# hud_v300_MCU.net
KiCad netlist of a schematic drawn in Altium Designer
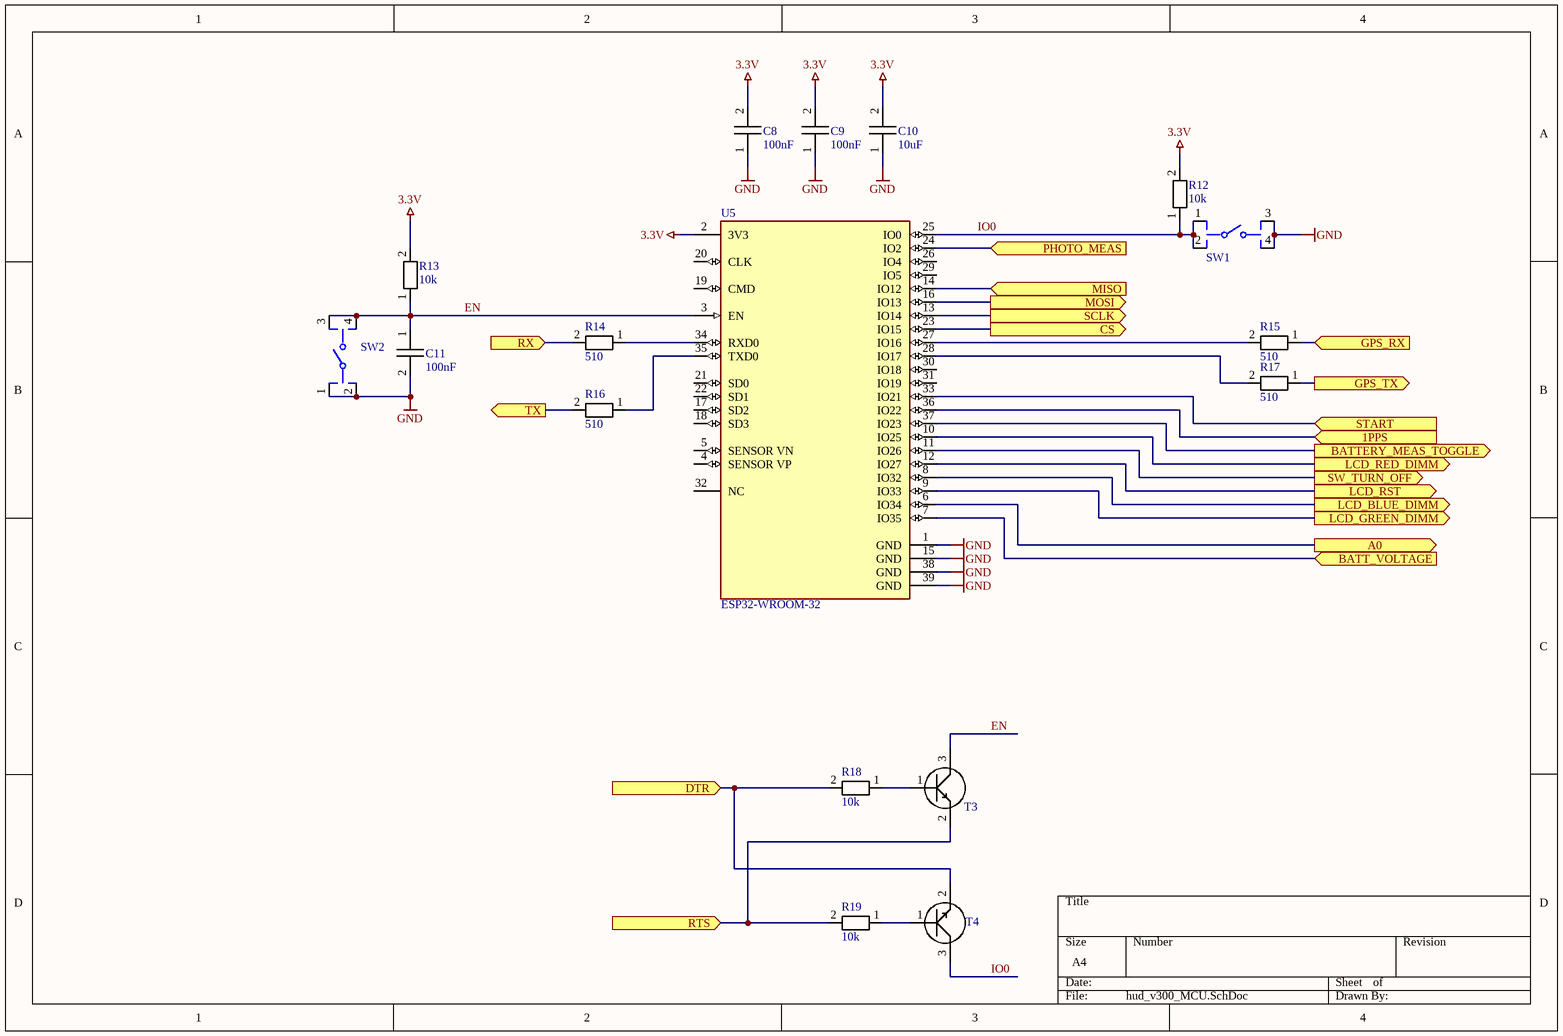
[diagram p0: hud_v300_MCU.SchDoc]

(export (version "E")
  (design (tool "Eeschema 10.0.6"))
  (components
    (comp (ref "C8") (value "100nF") (footprint "0805_C") (libsource (lib "Schlib1") (part "CAPACITOR")))
    (comp (ref "C9") (value "100nF") (footprint "0805_C") (libsource (lib "Schlib1") (part "CAPACITOR")))
    (comp (ref "C10") (value "10uF") (footprint "1210_C") (libsource (lib "Schlib1") (part "CAPACITOR")))
    (comp (ref "C11") (value "100nF") (footprint "0805_C") (libsource (lib "Schlib1") (part "CAPACITOR")))
    (comp (ref "R12") (value "10k") (footprint "0805") (libsource (lib "Schlib1") (part "RESISTOR")))
    (comp (ref "R13") (value "10k") (footprint "0805") (libsource (lib "Schlib1") (part "RESISTOR")))
    (comp (ref "R14") (value "510") (footprint "0805") (libsource (lib "Schlib1") (part "RESISTOR")))
    (comp (ref "R15") (value "510") (footprint "0805") (libsource (lib "Schlib1") (part "RESISTOR")))
    (comp (ref "R16") (value "510") (footprint "0805") (libsource (lib "Schlib1") (part "RESISTOR")))
    (comp (ref "R17") (value "510") (footprint "0805") (libsource (lib "Schlib1") (part "RESISTOR")))
    (comp (ref "R18") (value "10k") (footprint "0805") (libsource (lib "Schlib1") (part "RESISTOR")))
    (comp (ref "R19") (value "10k") (footprint "0805") (libsource (lib "Schlib1") (part "RESISTOR")))
    (comp (ref "SW1")
      (value "Switch_C&K_KSC241JLFS_eec")
      (footprint "C&K_KSC241JLFS")
      (description "SWITCH TACTILE SPST-NO 0.05A 32V")
      (fields (field (name "PART NUMBER") "KSC241JLFS") (field (name "MANUFACTURER") "C&K"))
      (libsource (lib "Schlib1") (part "Switch_C&K_KSC241JLFS_eec"))
    )
    (comp (ref "SW2")
      (value "Switch_C&K_KSC241JLFS_eec")
      (footprint "C&K_KSC241JLFS")
      (description "SWITCH TACTILE SPST-NO 0.05A 32V")
      (fields (field (name "PART NUMBER") "KSC241JLFS") (field (name "MANUFACTURER") "C&K"))
      (libsource (lib "Schlib1") (part "Switch_C&K_KSC241JLFS_eec"))
    )
    (comp (ref "T3") (value "BC848*") (footprint "SOT23") (libsource (lib "Schlib1") (part "TRANSISTOR_NPN")))
    (comp (ref "T4") (value "BC848*") (footprint "SOT23") (libsource (lib "Schlib1") (part "TRANSISTOR_NPN")))
    (comp (ref "U5")
      (value "ESP32-WROOM-32")
      (footprint "FP-ESP32-WROOM-32-MFG")
      (description "IC RF TXRX+MCU BLUETOOTH 48VFQFN")
      (libsource (lib "ic_modules") (part "ESP32-WROOM-32"))
    )
  )
  (nets
    (net (code "1") (name "/1PPS") (class "Default")
      (node (ref "U5") (pin "36") (pinfunction "IO22_36") (pintype "bidirectional"))
    )
    (net (code "2") (name "/A0") (class "Default")
      (node (ref "U5") (pin "6") (pinfunction "IO34_6") (pintype "bidirectional"))
    )
    (net (code "3") (name "/BATTERY_MEAS_TOGGLE") (class "Default")
      (node (ref "U5") (pin "37") (pinfunction "IO23_37") (pintype "bidirectional"))
    )
    (net (code "4") (name "/BATT_VOLTAGE") (class "Default")
      (node (ref "U5") (pin "7") (pinfunction "IO35_7") (pintype "bidirectional"))
    )
    (net (code "5") (name "/CS") (class "Default")
      (node (ref "U5") (pin "23") (pinfunction "IO15_23") (pintype "bidirectional"))
    )
    (net (code "6") (name "/DTR") (class "Default")
      (node (ref "R18") (pin "2") (pinfunction "1_2") (pintype "passive"))
      (node (ref "T4") (pin "2") (pinfunction "2_2") (pintype "passive"))
    )
    (net (code "7") (name "/EN") (class "Default")
      (node (ref "C11") (pin "1") (pinfunction "1_1") (pintype "passive"))
      (node (ref "R13") (pin "1") (pinfunction "0_1") (pintype "passive"))
      (node (ref "SW2") (pin "3") (pinfunction "3_3") (pintype "passive"))
      (node (ref "SW2") (pin "4") (pinfunction "4_4") (pintype "passive"))
      (node (ref "T3") (pin "3") (pinfunction "3_3") (pintype "passive"))
      (node (ref "U5") (pin "3") (pinfunction "EN_3") (pintype "input"))
    )
    (net (code "8") (name "/GPS_RX") (class "Default")
      (node (ref "R15") (pin "1") (pinfunction "0_1") (pintype "passive"))
    )
    (net (code "9") (name "/GPS_TX") (class "Default")
      (node (ref "R17") (pin "1") (pinfunction "0_1") (pintype "passive"))
    )
    (net (code "10") (name "/IO0") (class "Default")
      (node (ref "R12") (pin "1") (pinfunction "0_1") (pintype "passive"))
      (node (ref "SW1") (pin "1") (pinfunction "1_1") (pintype "passive"))
      (node (ref "SW1") (pin "2") (pinfunction "2_2") (pintype "passive"))
      (node (ref "T4") (pin "3") (pinfunction "3_3") (pintype "passive"))
      (node (ref "U5") (pin "25") (pinfunction "IO0_25") (pintype "bidirectional"))
    )
    (net (code "11") (name "/LCD_BLUE_DIMM") (class "Default")
      (node (ref "U5") (pin "8") (pinfunction "IO32_8") (pintype "bidirectional"))
    )
    (net (code "12") (name "/LCD_GREEN_DIMM") (class "Default")
      (node (ref "U5") (pin "9") (pinfunction "IO33_9") (pintype "bidirectional"))
    )
    (net (code "13") (name "/LCD_RED_DIMM") (class "Default")
      (node (ref "U5") (pin "10") (pinfunction "IO25_10") (pintype "bidirectional"))
    )
    (net (code "14") (name "/LCD_RST") (class "Default")
      (node (ref "U5") (pin "12") (pinfunction "IO27_12") (pintype "bidirectional"))
    )
    (net (code "15") (name "/MISO") (class "Default")
      (node (ref "U5") (pin "14") (pinfunction "IO12_14") (pintype "bidirectional"))
    )
    (net (code "16") (name "/MOSI") (class "Default")
      (node (ref "U5") (pin "16") (pinfunction "IO13_16") (pintype "bidirectional"))
    )
    (net (code "17") (name "/PHOTO_MEAS") (class "Default")
      (node (ref "U5") (pin "24") (pinfunction "IO2_24") (pintype "bidirectional"))
    )
    (net (code "18") (name "/RTS") (class "Default")
      (node (ref "R19") (pin "2") (pinfunction "1_2") (pintype "passive"))
      (node (ref "T3") (pin "2") (pinfunction "2_2") (pintype "passive"))
    )
    (net (code "19") (name "/RX") (class "Default")
      (node (ref "R14") (pin "2") (pinfunction "1_2") (pintype "passive"))
    )
    (net (code "20") (name "/SCLK") (class "Default")
      (node (ref "U5") (pin "13") (pinfunction "IO14_13") (pintype "bidirectional"))
    )
    (net (code "21") (name "/START") (class "Default")
      (node (ref "U5") (pin "33") (pinfunction "IO21_33") (pintype "bidirectional"))
    )
    (net (code "22") (name "/SW_TURN_OFF") (class "Default")
      (node (ref "U5") (pin "11") (pinfunction "IO26_11") (pintype "bidirectional"))
    )
    (net (code "23") (name "/TX") (class "Default")
      (node (ref "R16") (pin "2") (pinfunction "1_2") (pintype "passive"))
    )
    (net (code "24") (name "3.3V") (class "Default")
      (node (ref "C10") (pin "2") (pinfunction "2_2") (pintype "passive"))
      (node (ref "C8") (pin "2") (pinfunction "2_2") (pintype "passive"))
      (node (ref "C9") (pin "2") (pinfunction "2_2") (pintype "passive"))
      (node (ref "R12") (pin "2") (pinfunction "1_2") (pintype "passive"))
      (node (ref "R13") (pin "2") (pinfunction "1_2") (pintype "passive"))
      (node (ref "U5") (pin "2") (pinfunction "3V3_2") (pintype "power_in"))
    )
    (net (code "25") (name "GND") (class "Default")
      (node (ref "C10") (pin "1") (pinfunction "1_1") (pintype "passive"))
      (node (ref "C11") (pin "2") (pinfunction "2_2") (pintype "passive"))
      (node (ref "C8") (pin "1") (pinfunction "1_1") (pintype "passive"))
      (node (ref "C9") (pin "1") (pinfunction "1_1") (pintype "passive"))
      (node (ref "SW1") (pin "3") (pinfunction "3_3") (pintype "passive"))
      (node (ref "SW1") (pin "4") (pinfunction "4_4") (pintype "passive"))
      (node (ref "SW2") (pin "1") (pinfunction "1_1") (pintype "passive"))
      (node (ref "SW2") (pin "2") (pinfunction "2_2") (pintype "passive"))
      (node (ref "U5") (pin "1") (pinfunction "GND_1") (pintype "power_in"))
      (node (ref "U5") (pin "15") (pinfunction "GND_15") (pintype "power_in"))
      (node (ref "U5") (pin "38") (pinfunction "GND_38") (pintype "power_in"))
      (node (ref "U5") (pin "39") (pinfunction "GND_39") (pintype "power_in"))
    )
    (net (code "26") (name "Net-(R14-0)") (class "Default")
      (node (ref "R14") (pin "1") (pinfunction "0_1") (pintype "passive"))
      (node (ref "U5") (pin "34") (pinfunction "RXD0_34") (pintype "bidirectional"))
    )
    (net (code "27") (name "Net-(R15-1)") (class "Default")
      (node (ref "R15") (pin "2") (pinfunction "1_2") (pintype "passive"))
      (node (ref "U5") (pin "27") (pinfunction "IO16_27") (pintype "bidirectional"))
    )
    (net (code "28") (name "Net-(R16-0)") (class "Default")
      (node (ref "R16") (pin "1") (pinfunction "0_1") (pintype "passive"))
      (node (ref "U5") (pin "35") (pinfunction "TXD0_35") (pintype "bidirectional"))
    )
    (net (code "29") (name "Net-(R17-1)") (class "Default")
      (node (ref "R17") (pin "2") (pinfunction "1_2") (pintype "passive"))
      (node (ref "U5") (pin "28") (pinfunction "IO17_28") (pintype "bidirectional"))
    )
    (net (code "30") (name "Net-(R18-0)") (class "Default")
      (node (ref "R18") (pin "1") (pinfunction "0_1") (pintype "passive"))
      (node (ref "T3") (pin "1") (pinfunction "1_1") (pintype "passive"))
    )
    (net (code "31") (name "Net-(R19-0)") (class "Default")
      (node (ref "R19") (pin "1") (pinfunction "0_1") (pintype "passive"))
      (node (ref "T4") (pin "1") (pinfunction "1_1") (pintype "passive"))
    )
    (net (code "32") (name "unconnected-(U5-CLK-Pad20)") (class "Default")
      (node (ref "U5") (pin "20") (pinfunction "CLK_20") (pintype "bidirectional"))
    )
    (net (code "33") (name "unconnected-(U5-CMD-Pad19)") (class "Default")
      (node (ref "U5") (pin "19") (pinfunction "CMD_19") (pintype "bidirectional"))
    )
    (net (code "34") (name "unconnected-(U5-IO4-Pad26)") (class "Default")
      (node (ref "U5") (pin "26") (pinfunction "IO4_26") (pintype "bidirectional"))
    )
    (net (code "35") (name "unconnected-(U5-IO5-Pad29)") (class "Default")
      (node (ref "U5") (pin "29") (pinfunction "IO5_29") (pintype "bidirectional"))
    )
    (net (code "36") (name "unconnected-(U5-IO18-Pad30)") (class "Default")
      (node (ref "U5") (pin "30") (pinfunction "IO18_30") (pintype "bidirectional"))
    )
    (net (code "37") (name "unconnected-(U5-IO19-Pad31)") (class "Default")
      (node (ref "U5") (pin "31") (pinfunction "IO19_31") (pintype "bidirectional"))
    )
    (net (code "38") (name "unconnected-(U5-NC-Pad32)") (class "Default")
      (node (ref "U5") (pin "32") (pinfunction "NC_32") (pintype "passive"))
    )
    (net (code "39") (name "unconnected-(U5-SD0-Pad21)") (class "Default")
      (node (ref "U5") (pin "21") (pinfunction "SD0_21") (pintype "bidirectional"))
    )
    (net (code "40") (name "unconnected-(U5-SD1-Pad22)") (class "Default")
      (node (ref "U5") (pin "22") (pinfunction "SD1_22") (pintype "bidirectional"))
    )
    (net (code "41") (name "unconnected-(U5-SD2-Pad17)") (class "Default")
      (node (ref "U5") (pin "17") (pinfunction "SD2_17") (pintype "bidirectional"))
    )
    (net (code "42") (name "unconnected-(U5-SD3-Pad18)") (class "Default")
      (node (ref "U5") (pin "18") (pinfunction "SD3_18") (pintype "bidirectional"))
    )
    (net (code "43") (name "unconnected-(U5-SENSOR_VN-Pad5)") (class "Default")
      (node (ref "U5") (pin "5") (pinfunction "SENSOR_VN_5") (pintype "bidirectional"))
    )
    (net (code "44") (name "unconnected-(U5-SENSOR_VP-Pad4)") (class "Default")
      (node (ref "U5") (pin "4") (pinfunction "SENSOR_VP_4") (pintype "bidirectional"))
    )
  )
)
